# LICL_Int.net
KiCad netlist of a schematic drawn in EAGLE
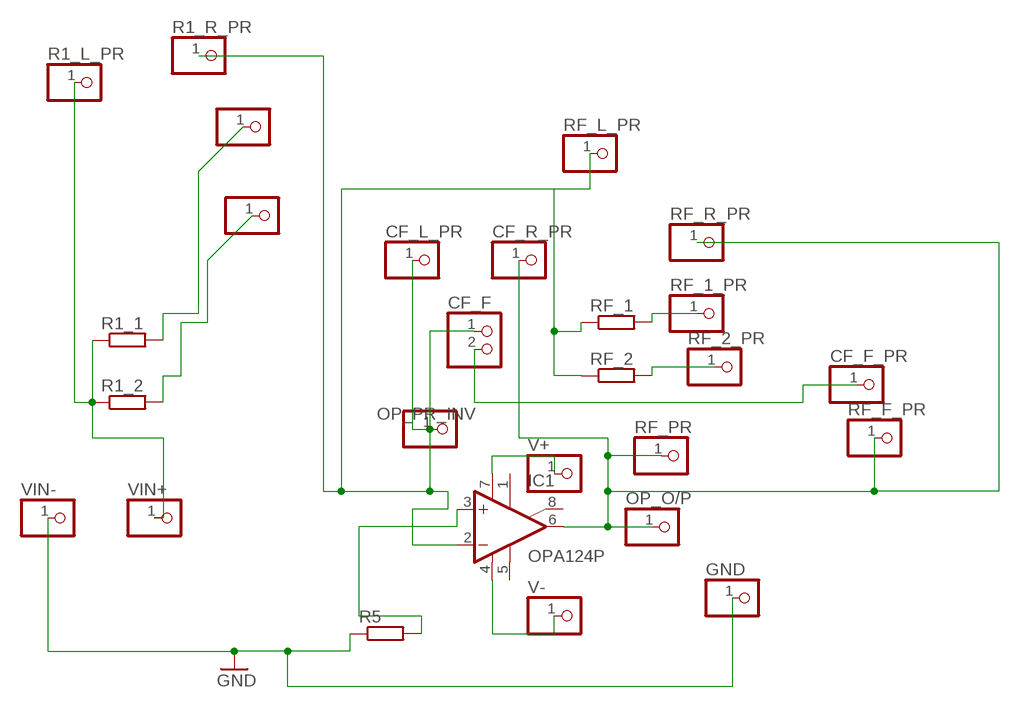
[diagram p0: schematic, sheet 1]

(export (version "E")
  (design (tool "Eeschema 10.0.6"))
  (components
    (comp (ref "CF_F")
      (value "PINHD-1X2")
      (footprint "eagle-import:1X02")
      (libsource (lib "eagle-import") (part "PINHD-1X2"))
    )
    (comp (ref "CF_F_PR")
      (value "PINHD-1X1")
      (footprint "eagle-import:1X01")
      (libsource (lib "eagle-import") (part "PINHD-1X1"))
    )
    (comp (ref "CF_L_PR")
      (value "PINHD-1X1")
      (footprint "eagle-import:1X01")
      (libsource (lib "eagle-import") (part "PINHD-1X1"))
    )
    (comp (ref "CF_R_PR")
      (value "PINHD-1X1")
      (footprint "eagle-import:1X01")
      (libsource (lib "eagle-import") (part "PINHD-1X1"))
    )
    (comp (ref "GND")
      (value "PINHD-1X1")
      (footprint "eagle-import:1X01")
      (libsource (lib "eagle-import") (part "PINHD-1X1"))
    )
    (comp (ref "IC1")
      (value "OPA124P")
      (footprint "eagle-import:DIL08")
      (libsource (lib "eagle-import") (part "OPA124P"))
    )
    (comp (ref "OP_O/P")
      (value "PINHD-1X1")
      (footprint "eagle-import:1X01")
      (libsource (lib "eagle-import") (part "PINHD-1X1"))
    )
    (comp (ref "R1_1")
      (value "R-EU_0207/10")
      (footprint "eagle-import:0207_10")
      (libsource (lib "eagle-import") (part "R-EU_0207/10"))
    )
    (comp (ref "R1_1_PR")
      (value "PINHD-1X1")
      (footprint "eagle-import:1X01")
      (libsource (lib "eagle-import") (part "PINHD-1X1"))
    )
    (comp (ref "R1_2")
      (value "R-EU_0207/10")
      (footprint "eagle-import:0207_10")
      (libsource (lib "eagle-import") (part "R-EU_0207/10"))
    )
    (comp (ref "R1_2_PR")
      (value "PINHD-1X1")
      (footprint "eagle-import:1X01")
      (libsource (lib "eagle-import") (part "PINHD-1X1"))
    )
    (comp (ref "R1_L_PR")
      (value "PINHD-1X1")
      (footprint "eagle-import:1X01")
      (libsource (lib "eagle-import") (part "PINHD-1X1"))
    )
    (comp (ref "R1_PR")
      (value "PINHD-1X1")
      (footprint "eagle-import:1X01")
      (libsource (lib "eagle-import") (part "PINHD-1X1"))
    )
    (comp (ref "R1_R_PR")
      (value "PINHD-1X1")
      (footprint "eagle-import:1X01")
      (libsource (lib "eagle-import") (part "PINHD-1X1"))
    )
    (comp (ref "R5")
      (value "R-EU_0207/10")
      (footprint "eagle-import:0207_10")
      (libsource (lib "eagle-import") (part "R-EU_0207/10"))
    )
    (comp (ref "RF_1")
      (value "R-EU_0207/10")
      (footprint "eagle-import:0207_10")
      (libsource (lib "eagle-import") (part "R-EU_0207/10"))
    )
    (comp (ref "RF_1_PR")
      (value "PINHD-1X1")
      (footprint "eagle-import:1X01")
      (libsource (lib "eagle-import") (part "PINHD-1X1"))
    )
    (comp (ref "RF_2")
      (value "R-EU_0207/10")
      (footprint "eagle-import:0207_10")
      (libsource (lib "eagle-import") (part "R-EU_0207/10"))
    )
    (comp (ref "RF_2_PR")
      (value "PINHD-1X1")
      (footprint "eagle-import:1X01")
      (libsource (lib "eagle-import") (part "PINHD-1X1"))
    )
    (comp (ref "RF_F_PR")
      (value "PINHD-1X1")
      (footprint "eagle-import:1X01")
      (libsource (lib "eagle-import") (part "PINHD-1X1"))
    )
    (comp (ref "RF_L_PR")
      (value "PINHD-1X1")
      (footprint "eagle-import:1X01")
      (libsource (lib "eagle-import") (part "PINHD-1X1"))
    )
    (comp (ref "RF_PR")
      (value "PINHD-1X1")
      (footprint "eagle-import:1X01")
      (libsource (lib "eagle-import") (part "PINHD-1X1"))
    )
    (comp (ref "RF_R_PR")
      (value "PINHD-1X1")
      (footprint "eagle-import:1X01")
      (libsource (lib "eagle-import") (part "PINHD-1X1"))
    )
    (comp (ref "V+")
      (value "PINHD-1X1")
      (footprint "eagle-import:1X01")
      (libsource (lib "eagle-import") (part "PINHD-1X1"))
    )
    (comp (ref "V-")
      (value "PINHD-1X1")
      (footprint "eagle-import:1X01")
      (libsource (lib "eagle-import") (part "PINHD-1X1"))
    )
    (comp (ref "VIN+")
      (value "PINHD-1X1")
      (footprint "eagle-import:1X01")
      (libsource (lib "eagle-import") (part "PINHD-1X1"))
    )
    (comp (ref "VIN-")
      (value "PINHD-1X1")
      (footprint "eagle-import:1X01")
      (libsource (lib "eagle-import") (part "PINHD-1X1"))
    )
  )
  (nets
    (net (code "1") (name "/OP_PR_INV") (class "Default")
      (node (ref "CF_F") (pin "1") (pinfunction "1_1") (pintype "passive"))
      (node (ref "CF_L_PR") (pin "1") (pinfunction "1_1") (pintype "passive"))
      (node (ref "IC1") (pin "2") (pinfunction "-IN_2") (pintype "input"))
      (node (ref "R1_PR") (pin "1") (pinfunction "1_1") (pintype "passive"))
      (node (ref "R1_R_PR") (pin "1") (pinfunction "1_1") (pintype "passive"))
      (node (ref "RF_1") (pin "1") (pinfunction "1_1") (pintype "passive"))
      (node (ref "RF_2") (pin "1") (pinfunction "1_1") (pintype "passive"))
      (node (ref "RF_L_PR") (pin "1") (pinfunction "1_1") (pintype "passive"))
    )
    (net (code "2") (name "GND") (class "Default")
      (node (ref "GND") (pin "1") (pinfunction "1_1") (pintype "passive"))
      (node (ref "R5") (pin "1") (pinfunction "1_1") (pintype "passive"))
      (node (ref "VIN-") (pin "1") (pinfunction "1_1") (pintype "passive"))
    )
    (net (code "3") (name "Net-(CF_F-Pad2)") (class "Default")
      (node (ref "CF_F") (pin "2") (pinfunction "2_2") (pintype "passive"))
      (node (ref "CF_F_PR") (pin "1") (pinfunction "1_1") (pintype "passive"))
    )
    (net (code "4") (name "Net-(IC1-+IN)") (class "Default")
      (node (ref "IC1") (pin "3") (pinfunction "+IN_3") (pintype "input"))
      (node (ref "R5") (pin "2") (pinfunction "2_2") (pintype "passive"))
    )
    (net (code "5") (name "Net-(IC1-OUT)") (class "Default")
      (node (ref "CF_R_PR") (pin "1") (pinfunction "1_1") (pintype "passive"))
      (node (ref "IC1") (pin "6") (pinfunction "OUT_6") (pintype "output"))
      (node (ref "OP_O/P") (pin "1") (pinfunction "1_1") (pintype "passive"))
      (node (ref "RF_F_PR") (pin "1") (pinfunction "1_1") (pintype "passive"))
      (node (ref "RF_PR") (pin "1") (pinfunction "1_1") (pintype "passive"))
      (node (ref "RF_R_PR") (pin "1") (pinfunction "1_1") (pintype "passive"))
    )
    (net (code "6") (name "Net-(IC1-V+)") (class "Default")
      (node (ref "IC1") (pin "7") (pinfunction "V+_7") (pintype "power_in"))
      (node (ref "V+") (pin "1") (pinfunction "1_1") (pintype "passive"))
    )
    (net (code "7") (name "Net-(IC1-V-)") (class "Default")
      (node (ref "IC1") (pin "4") (pinfunction "V-_4") (pintype "power_in"))
      (node (ref "V-") (pin "1") (pinfunction "1_1") (pintype "passive"))
    )
    (net (code "8") (name "Net-(R1_1-Pad1)") (class "Default")
      (node (ref "R1_1") (pin "1") (pinfunction "1_1") (pintype "passive"))
      (node (ref "R1_2") (pin "1") (pinfunction "1_1") (pintype "passive"))
      (node (ref "R1_L_PR") (pin "1") (pinfunction "1_1") (pintype "passive"))
      (node (ref "VIN+") (pin "1") (pinfunction "1_1") (pintype "passive"))
    )
    (net (code "9") (name "Net-(R1_1-Pad2)") (class "Default")
      (node (ref "R1_1") (pin "2") (pinfunction "2_2") (pintype "passive"))
      (node (ref "R1_1_PR") (pin "1") (pinfunction "1_1") (pintype "passive"))
    )
    (net (code "10") (name "Net-(R1_2-Pad2)") (class "Default")
      (node (ref "R1_2") (pin "2") (pinfunction "2_2") (pintype "passive"))
      (node (ref "R1_2_PR") (pin "1") (pinfunction "1_1") (pintype "passive"))
    )
    (net (code "11") (name "Net-(RF_1-Pad2)") (class "Default")
      (node (ref "RF_1") (pin "2") (pinfunction "2_2") (pintype "passive"))
      (node (ref "RF_1_PR") (pin "1") (pinfunction "1_1") (pintype "passive"))
    )
    (net (code "12") (name "Net-(RF_2-Pad2)") (class "Default")
      (node (ref "RF_2") (pin "2") (pinfunction "2_2") (pintype "passive"))
      (node (ref "RF_2_PR") (pin "1") (pinfunction "1_1") (pintype "passive"))
    )
    (net (code "13") (name "unconnected-(IC1-SUBS-Pad8)") (class "Default")
      (node (ref "IC1") (pin "8") (pinfunction "SUBS_8") (pintype "passive"))
    )
    (net (code "14") (name "unconnected-(IC1-TRIM1-Pad1)") (class "Default")
      (node (ref "IC1") (pin "1") (pinfunction "TRIM1_1") (pintype "passive"))
    )
    (net (code "15") (name "unconnected-(IC1-TRIM2-Pad5)") (class "Default")
      (node (ref "IC1") (pin "5") (pinfunction "TRIM2_5") (pintype "passive"))
    )
  )
)
